# fdc6326l_breakout.net
KiCad netlist of a schematic drawn in EAGLE
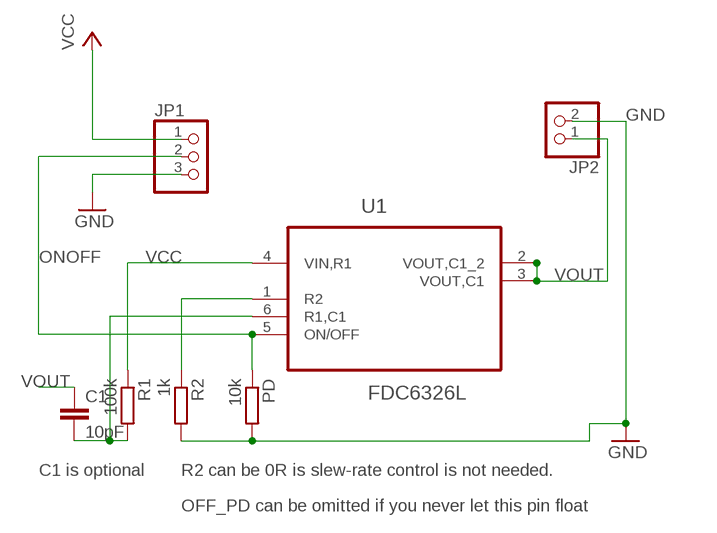
[diagram p0: schematic, sheet 1]

(export (version "E")
  (design (tool "Eeschema 10.0.6"))
  (components
    (comp (ref "C1")
      (value "10pF")
      (footprint "eagle-import:C0603")
      (libsource (lib "eagle-import") (part "C-EUC0603"))
    )
    (comp (ref "JP1")
      (value "PINHD-1X3")
      (footprint "eagle-import:1X03")
      (libsource (lib "eagle-import") (part "PINHD-1X3"))
    )
    (comp (ref "JP2")
      (value "PINHD-1X2")
      (footprint "eagle-import:1X02")
      (libsource (lib "eagle-import") (part "PINHD-1X2"))
    )
    (comp (ref "PD")
      (value "10k")
      (footprint "eagle-import:R0603")
      (libsource (lib "eagle-import") (part "R-EU_R0603"))
    )
    (comp (ref "R1")
      (value "100k")
      (footprint "eagle-import:R0603")
      (libsource (lib "eagle-import") (part "R-EU_R0603"))
    )
    (comp (ref "R2")
      (value "1k")
      (footprint "eagle-import:R0603")
      (libsource (lib "eagle-import") (part "R-EU_R0603"))
    )
    (comp (ref "U1")
      (value "FDC6326L")
      (footprint "eagle-import:SOT95P280X110-6N")
      (libsource (lib "eagle-import") (part "FDC6326L"))
    )
  )
  (nets
    (net (code "1") (name "/ONOFF") (class "Default")
      (node (ref "JP1") (pin "2") (pinfunction "2_2") (pintype "passive"))
      (node (ref "PD") (pin "1") (pinfunction "1_1") (pintype "passive"))
      (node (ref "U1") (pin "5") (pinfunction "ON/OFF_5") (pintype "input"))
    )
    (net (code "2") (name "/VOUT") (class "Default")
      (node (ref "C1") (pin "1") (pinfunction "1_1") (pintype "passive"))
      (node (ref "JP2") (pin "1") (pinfunction "1_1") (pintype "passive"))
      (node (ref "U1") (pin "2") (pinfunction "VOUT,C1_2_2") (pintype "output"))
      (node (ref "U1") (pin "3") (pinfunction "VOUT,C1_3") (pintype "output"))
    )
    (net (code "3") (name "GND") (class "Default")
      (node (ref "JP1") (pin "3") (pinfunction "3_3") (pintype "passive"))
      (node (ref "JP2") (pin "2") (pinfunction "2_2") (pintype "passive"))
      (node (ref "PD") (pin "2") (pinfunction "2_2") (pintype "passive"))
      (node (ref "R2") (pin "2") (pinfunction "2_2") (pintype "passive"))
    )
    (net (code "4") (name "Net-(U1-R1,C1)") (class "Default")
      (node (ref "C1") (pin "2") (pinfunction "2_2") (pintype "passive"))
      (node (ref "R1") (pin "2") (pinfunction "2_2") (pintype "passive"))
      (node (ref "U1") (pin "6") (pinfunction "R1,C1_6") (pintype "input"))
    )
    (net (code "5") (name "Net-(U1-R2)") (class "Default")
      (node (ref "R2") (pin "1") (pinfunction "1_1") (pintype "passive"))
      (node (ref "U1") (pin "1") (pinfunction "R2_1") (pintype "input"))
    )
    (net (code "6") (name "VCC") (class "Default")
      (node (ref "JP1") (pin "1") (pinfunction "1_1") (pintype "passive"))
      (node (ref "R1") (pin "1") (pinfunction "1_1") (pintype "passive"))
      (node (ref "U1") (pin "4") (pinfunction "VIN,R1_4") (pintype "power_in"))
    )
  )
)
